# mk_bt.net
KiCad netlist of a schematic drawn in EAGLE
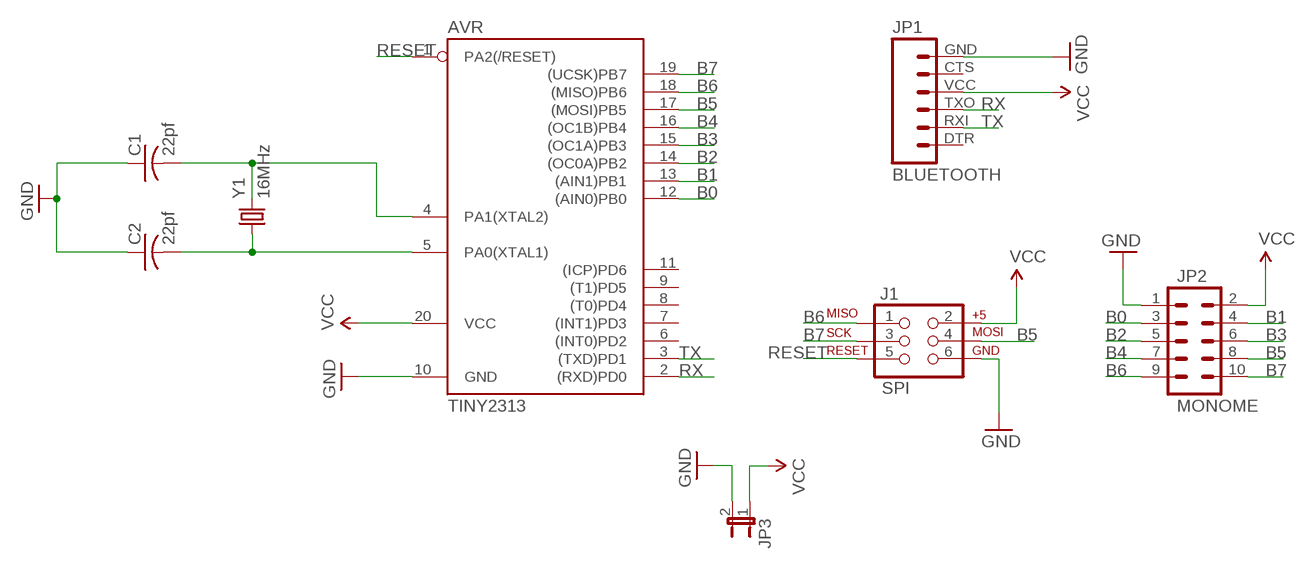
[diagram p0: schematic, sheet 1]

(export (version "E")
  (design (tool "Eeschema 10.0.6"))
  (components
    (comp (ref "AVR")
      (value "TINY2313")
      (footprint "eagle-import:DIL20")
      (libsource (lib "eagle-import") (part "TINY2313-P"))
    )
    (comp (ref "C1")
      (value "22pf")
      (footprint "eagle-import:C025-025X050")
      (libsource (lib "eagle-import") (part "C-US025-025X050"))
    )
    (comp (ref "C2")
      (value "22pf")
      (footprint "eagle-import:C025-025X050")
      (libsource (lib "eagle-import") (part "C-US025-025X050"))
    )
    (comp (ref "J1")
      (value "SPI")
      (footprint "eagle-import:2X3")
      (libsource (lib "eagle-import") (part "AVR_SPI_PRG_6PTH"))
    )
    (comp (ref "JP1")
      (value "BLUETOOTH")
      (footprint "eagle-import:FTDI_BASIC")
      (libsource (lib "eagle-import") (part "FTDI_BASICPTH"))
    )
    (comp (ref "JP2")
      (value "MONOME")
      (footprint "eagle-import:2X5-SHROUDED")
      (libsource (lib "eagle-import") (part "M05X2SHD"))
    )
    (comp (ref "JP3")
      (value "JUMPER-2PTH")
      (footprint "eagle-import:1X02")
      (libsource (lib "eagle-import") (part "JUMPER-2PTH"))
    )
    (comp (ref "Y1")
      (value "16MHz")
      (footprint "eagle-import:HC49US")
      (libsource (lib "eagle-import") (part "CRYSTALHC49US"))
    )
  )
  (nets
    (net (code "1") (name "/B0") (class "Default")
      (node (ref "AVR") (pin "12") (pinfunction "(AIN0)PB0_12") (pintype "bidirectional"))
      (node (ref "JP2") (pin "3") (pinfunction "3_3") (pintype "passive"))
    )
    (net (code "2") (name "/B1") (class "Default")
      (node (ref "AVR") (pin "13") (pinfunction "(AIN1)PB1_13") (pintype "bidirectional"))
      (node (ref "JP2") (pin "4") (pinfunction "4_4") (pintype "passive"))
    )
    (net (code "3") (name "/B2") (class "Default")
      (node (ref "AVR") (pin "14") (pinfunction "(OC0A)PB2_14") (pintype "bidirectional"))
      (node (ref "JP2") (pin "5") (pinfunction "5_5") (pintype "passive"))
    )
    (net (code "4") (name "/B3") (class "Default")
      (node (ref "AVR") (pin "15") (pinfunction "(OC1A)PB3_15") (pintype "bidirectional"))
      (node (ref "JP2") (pin "6") (pinfunction "6_6") (pintype "passive"))
    )
    (net (code "5") (name "/B4") (class "Default")
      (node (ref "AVR") (pin "16") (pinfunction "(OC1B)PB4_16") (pintype "bidirectional"))
      (node (ref "JP2") (pin "7") (pinfunction "7_7") (pintype "passive"))
    )
    (net (code "6") (name "/B5") (class "Default")
      (node (ref "AVR") (pin "17") (pinfunction "(MOSI)PB5_17") (pintype "bidirectional"))
      (node (ref "J1") (pin "4") (pinfunction "4_4") (pintype "passive"))
      (node (ref "JP2") (pin "8") (pinfunction "8_8") (pintype "passive"))
    )
    (net (code "7") (name "/B6") (class "Default")
      (node (ref "AVR") (pin "18") (pinfunction "(MISO)PB6_18") (pintype "bidirectional"))
      (node (ref "J1") (pin "1") (pinfunction "1_1") (pintype "passive"))
      (node (ref "JP2") (pin "9") (pinfunction "9_9") (pintype "passive"))
    )
    (net (code "8") (name "/B7") (class "Default")
      (node (ref "AVR") (pin "19") (pinfunction "(UCSK)PB7_19") (pintype "bidirectional"))
      (node (ref "J1") (pin "3") (pinfunction "3_3") (pintype "passive"))
      (node (ref "JP2") (pin "10") (pinfunction "10_10") (pintype "passive"))
    )
    (net (code "9") (name "/RESET") (class "Default")
      (node (ref "AVR") (pin "1") (pinfunction "PA2(/RESET)_1") (pintype "input"))
      (node (ref "J1") (pin "5") (pinfunction "5_5") (pintype "passive"))
    )
    (net (code "10") (name "/RX") (class "Default")
      (node (ref "AVR") (pin "2") (pinfunction "(RXD)PD0_2") (pintype "bidirectional"))
      (node (ref "JP1") (pin "TXO") (pinfunction "3_TXO") (pintype "passive"))
    )
    (net (code "11") (name "/TX") (class "Default")
      (node (ref "AVR") (pin "3") (pinfunction "(TXD)PD1_3") (pintype "bidirectional"))
      (node (ref "JP1") (pin "RXI") (pinfunction "2_RXI") (pintype "passive"))
    )
    (net (code "12") (name "GND") (class "Default")
      (node (ref "AVR") (pin "10") (pinfunction "GND_10") (pintype "power_in"))
      (node (ref "C1") (pin "1") (pinfunction "1_1") (pintype "passive"))
      (node (ref "C2") (pin "1") (pinfunction "1_1") (pintype "passive"))
      (node (ref "J1") (pin "6") (pinfunction "6_6") (pintype "passive"))
      (node (ref "JP1") (pin "GND") (pinfunction "6_GND") (pintype "passive"))
      (node (ref "JP2") (pin "1") (pinfunction "1_1") (pintype "passive"))
      (node (ref "JP3") (pin "2") (pinfunction "2_2") (pintype "passive"))
    )
    (net (code "13") (name "Net-(AVR-PA0(XTAL1))") (class "Default")
      (node (ref "AVR") (pin "5") (pinfunction "PA0(XTAL1)_5") (pintype "bidirectional"))
      (node (ref "C2") (pin "2") (pinfunction "2_2") (pintype "passive"))
      (node (ref "Y1") (pin "1") (pinfunction "1_1") (pintype "passive"))
    )
    (net (code "14") (name "Net-(AVR-PA1(XTAL2))") (class "Default")
      (node (ref "AVR") (pin "4") (pinfunction "PA1(XTAL2)_4") (pintype "bidirectional"))
      (node (ref "C1") (pin "2") (pinfunction "2_2") (pintype "passive"))
      (node (ref "Y1") (pin "2") (pinfunction "2_2") (pintype "passive"))
    )
    (net (code "15") (name "VCC") (class "Default")
      (node (ref "AVR") (pin "20") (pinfunction "VCC_20") (pintype "power_in"))
      (node (ref "J1") (pin "2") (pinfunction "2_2") (pintype "passive"))
      (node (ref "JP1") (pin "VCC") (pinfunction "4_VCC") (pintype "passive"))
      (node (ref "JP2") (pin "2") (pinfunction "2_2") (pintype "passive"))
      (node (ref "JP3") (pin "1") (pinfunction "1_1") (pintype "passive"))
    )
    (net (code "16") (name "unconnected-(AVR-(ICP)PD6-Pad11)") (class "Default")
      (node (ref "AVR") (pin "11") (pinfunction "(ICP)PD6_11") (pintype "bidirectional"))
    )
    (net (code "17") (name "unconnected-(AVR-(INT0)PD2-Pad6)") (class "Default")
      (node (ref "AVR") (pin "6") (pinfunction "(INT0)PD2_6") (pintype "bidirectional"))
    )
    (net (code "18") (name "unconnected-(AVR-(INT1)PD3-Pad7)") (class "Default")
      (node (ref "AVR") (pin "7") (pinfunction "(INT1)PD3_7") (pintype "bidirectional"))
    )
    (net (code "19") (name "unconnected-(AVR-(T0)PD4-Pad8)") (class "Default")
      (node (ref "AVR") (pin "8") (pinfunction "(T0)PD4_8") (pintype "bidirectional"))
    )
    (net (code "20") (name "unconnected-(AVR-(T1)PD5-Pad9)") (class "Default")
      (node (ref "AVR") (pin "9") (pinfunction "(T1)PD5_9") (pintype "bidirectional"))
    )
    (net (code "21") (name "unconnected-(JP1-1-PadDTR)") (class "Default")
      (node (ref "JP1") (pin "DTR") (pinfunction "1_DTR") (pintype "passive"))
    )
    (net (code "22") (name "unconnected-(JP1-5-PadCTS)") (class "Default")
      (node (ref "JP1") (pin "CTS") (pinfunction "5_CTS") (pintype "passive"))
    )
  )
)
